# SWITCHING.net
KiCad netlist of a schematic drawn in Altium Designer
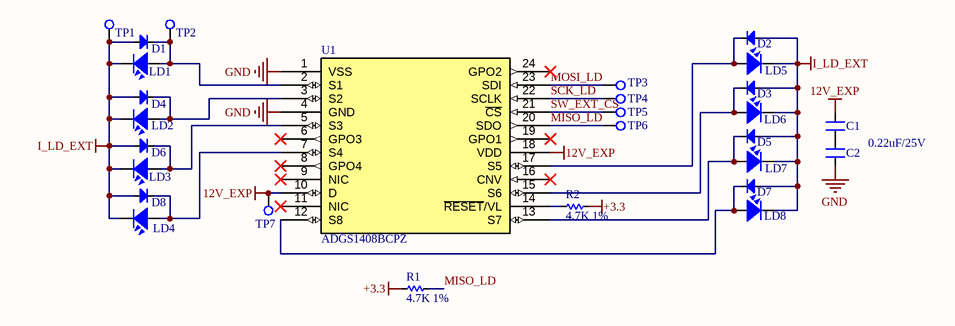
[diagram p0: SWITCHING.SchDoc]

(export (version "E")
  (design (tool "Eeschema 10.0.6"))
  (components
    (comp (ref "C1")
      (value "0.22uF/25V")
      (footprint "SM-0603")
      (description "0603")
      (libsource (lib "Capacitors") (part "CM"))
    )
    (comp (ref "C2")
      (value "0.22uF/25V")
      (footprint "SM-0603")
      (description "0603")
      (libsource (lib "Capacitors") (part "CM"))
    )
    (comp (ref "D1")
      (value "1N4148W-TP")
      (footprint "SOD23")
      (description "DIODE GEN PURP 100V 150MA SOD123")
      (fields (field (name "PUBLISHER") "Altium Limited"))
      (libsource (lib "Library") (part "Diode SMD"))
    )
    (comp (ref "D2")
      (value "1N4148W-TP")
      (footprint "SOD23")
      (description "DIODE GEN PURP 100V 150MA SOD123")
      (fields (field (name "PUBLISHER") "Altium Limited"))
      (libsource (lib "Library") (part "Diode SMD"))
    )
    (comp (ref "D3")
      (value "1N4148W-TP")
      (footprint "SOD23")
      (description "DIODE GEN PURP 100V 150MA SOD123")
      (fields (field (name "PUBLISHER") "Altium Limited"))
      (libsource (lib "Library") (part "Diode SMD"))
    )
    (comp (ref "D4")
      (value "1N4148W-TP")
      (footprint "SOD23")
      (description "DIODE GEN PURP 100V 150MA SOD123")
      (fields (field (name "PUBLISHER") "Altium Limited"))
      (libsource (lib "Library") (part "Diode SMD"))
    )
    (comp (ref "D5")
      (value "1N4148W-TP")
      (footprint "SOD23")
      (description "DIODE GEN PURP 100V 150MA SOD123")
      (fields (field (name "PUBLISHER") "Altium Limited"))
      (libsource (lib "Library") (part "Diode SMD"))
    )
    (comp (ref "D6")
      (value "1N4148W-TP")
      (footprint "SOD23")
      (description "DIODE GEN PURP 100V 150MA SOD123")
      (fields (field (name "PUBLISHER") "Altium Limited"))
      (libsource (lib "Library") (part "Diode SMD"))
    )
    (comp (ref "D7")
      (value "1N4148W-TP")
      (footprint "SOD23")
      (description "DIODE GEN PURP 100V 150MA SOD123")
      (fields (field (name "PUBLISHER") "Altium Limited"))
      (libsource (lib "Library") (part "Diode SMD"))
    )
    (comp (ref "D8")
      (value "1N4148W-TP")
      (footprint "SOD23")
      (description "DIODE GEN PURP 100V 150MA SOD123")
      (fields (field (name "PUBLISHER") "Altium Limited"))
      (libsource (lib "Library") (part "Diode SMD"))
    )
    (comp (ref "LD1") (value "LaserDiode") (footprint "LASER") (libsource (lib "Library") (part "LD")))
    (comp (ref "LD2") (value "LaserDiode") (footprint "LASER") (libsource (lib "Library") (part "LD")))
    (comp (ref "LD3") (value "LaserDiode") (footprint "LASER") (libsource (lib "Library") (part "LD")))
    (comp (ref "LD4") (value "LaserDiode") (footprint "LASER") (libsource (lib "Library") (part "LD")))
    (comp (ref "LD5") (value "LaserDiode") (footprint "LASER") (libsource (lib "Library") (part "LD")))
    (comp (ref "LD6") (value "LaserDiode") (footprint "LASER") (libsource (lib "Library") (part "LD")))
    (comp (ref "LD7") (value "LaserDiode") (footprint "LASER") (libsource (lib "Library") (part "LD")))
    (comp (ref "LD8") (value "LaserDiode") (footprint "LASER") (libsource (lib "Library") (part "LD")))
    (comp (ref "R1")
      (value "4.7K 1%")
      (footprint "RES-SMD-0603")
      (description "0603")
      (fields
        (field (name "MANUFACTURER") "Generic Components")
        (field (name "PUBLISHER") "Altium Hobart Technology Centre")
      )
      (libsource (lib "Library") (part "Res-SMD"))
    )
    (comp (ref "R2")
      (value "4.7K 1%")
      (footprint "RES-SMD-0603")
      (description "0603")
      (fields
        (field (name "MANUFACTURER") "Generic Components")
        (field (name "PUBLISHER") "Altium Hobart Technology Centre")
      )
      (libsource (lib "Library") (part "Res-SMD"))
    )
    (comp (ref "TP1")
      (value "Test_Point")
      (footprint "TESTPOINT")
      (libsource (lib "Library_HUNG") (part "Test_Point"))
    )
    (comp (ref "TP2")
      (value "Test_Point")
      (footprint "TESTPOINT")
      (libsource (lib "Library_HUNG") (part "Test_Point"))
    )
    (comp (ref "TP3")
      (value "Test_Point")
      (footprint "TESTPOINT")
      (libsource (lib "Library_HUNG") (part "Test_Point"))
    )
    (comp (ref "TP4")
      (value "Test_Point")
      (footprint "TESTPOINT")
      (libsource (lib "Library_HUNG") (part "Test_Point"))
    )
    (comp (ref "TP5")
      (value "Test_Point")
      (footprint "TESTPOINT")
      (libsource (lib "Library_HUNG") (part "Test_Point"))
    )
    (comp (ref "TP6")
      (value "Test_Point")
      (footprint "TESTPOINT")
      (libsource (lib "Library_HUNG") (part "Test_Point"))
    )
    (comp (ref "TP7")
      (value "Test_Point")
      (footprint "TESTPOINT")
      (libsource (lib "Library_HUNG") (part "Test_Point"))
    )
    (comp (ref "U1")
      (value "ADGS1408BCPZ")
      (footprint "ADGS1408BCPZ")
      (description "IC MUX 8:1 4.7OHM 24LFCSP")
      (libsource (lib "Library") (part "ADGS1408"))
    )
  )
  (nets
    (net (code "1") (name "+3.3") (class "Default")
      (node (ref "R1") (pin "2") (pinfunction "2_2") (pintype "passive"))
      (node (ref "R2") (pin "1") (pinfunction "1_1") (pintype "passive"))
    )
    (net (code "2") (name "/MISO_LD") (class "Default")
      (node (ref "R1") (pin "1") (pinfunction "1_1") (pintype "passive"))
      (node (ref "TP6") (pin "1") (pintype "power_in"))
      (node (ref "U1") (pin "20") (pinfunction "SDO_20") (pintype "output"))
    )
    (net (code "3") (name "/MOSI_LD") (class "Default")
      (node (ref "TP3") (pin "1") (pintype "power_in"))
      (node (ref "U1") (pin "23") (pinfunction "SDI_23") (pintype "input"))
    )
    (net (code "4") (name "/SCK_LD") (class "Default")
      (node (ref "TP4") (pin "1") (pintype "power_in"))
      (node (ref "U1") (pin "22") (pinfunction "SCLK_22") (pintype "input"))
    )
    (net (code "5") (name "/SW_EXT_CS") (class "Default")
      (node (ref "TP5") (pin "1") (pintype "power_in"))
      (node (ref "U1") (pin "21") (pinfunction "~{CS}_21") (pintype "input"))
    )
    (net (code "6") (name "12V_EXP") (class "Default")
      (node (ref "C1") (pin "2") (pinfunction "2_2") (pintype "passive"))
      (node (ref "TP7") (pin "1") (pintype "power_in"))
      (node (ref "U1") (pin "10") (pinfunction "D_10") (pintype "bidirectional"))
      (node (ref "U1") (pin "18") (pinfunction "VDD_18") (pintype "power_in"))
    )
    (net (code "7") (name "GND") (class "Default")
      (node (ref "C2") (pin "1") (pinfunction "1_1") (pintype "passive"))
      (node (ref "U1") (pin "1") (pinfunction "VSS_1") (pintype "power_in"))
      (node (ref "U1") (pin "4") (pinfunction "GND_4") (pintype "power_in"))
    )
    (net (code "8") (name "I_LD_EXT") (class "Default")
      (node (ref "D1") (pin "1") (pinfunction "A_1") (pintype "passive"))
      (node (ref "D2") (pin "1") (pinfunction "A_1") (pintype "passive"))
      (node (ref "D3") (pin "1") (pinfunction "A_1") (pintype "passive"))
      (node (ref "D4") (pin "1") (pinfunction "A_1") (pintype "passive"))
      (node (ref "D5") (pin "1") (pinfunction "A_1") (pintype "passive"))
      (node (ref "D6") (pin "1") (pinfunction "A_1") (pintype "passive"))
      (node (ref "D7") (pin "1") (pinfunction "A_1") (pintype "passive"))
      (node (ref "D8") (pin "1") (pinfunction "A_1") (pintype "passive"))
      (node (ref "LD1") (pin "3") (pinfunction "3_3") (pintype "passive"))
      (node (ref "LD2") (pin "3") (pinfunction "3_3") (pintype "passive"))
      (node (ref "LD3") (pin "3") (pinfunction "3_3") (pintype "passive"))
      (node (ref "LD4") (pin "3") (pinfunction "3_3") (pintype "passive"))
      (node (ref "LD5") (pin "3") (pinfunction "3_3") (pintype "passive"))
      (node (ref "LD6") (pin "3") (pinfunction "3_3") (pintype "passive"))
      (node (ref "LD7") (pin "3") (pinfunction "3_3") (pintype "passive"))
      (node (ref "LD8") (pin "3") (pinfunction "3_3") (pintype "passive"))
      (node (ref "TP1") (pin "1") (pintype "power_in"))
    )
    (net (code "9") (name "Net-(C1-Pad1)") (class "Default")
      (node (ref "C1") (pin "1") (pinfunction "1_1") (pintype "passive"))
      (node (ref "C2") (pin "2") (pinfunction "2_2") (pintype "passive"))
    )
    (net (code "10") (name "Net-(D1-K)") (class "Default")
      (node (ref "D1") (pin "2") (pinfunction "K_2") (pintype "passive"))
      (node (ref "LD1") (pin "1") (pinfunction "1_1") (pintype "passive"))
      (node (ref "TP2") (pin "1") (pintype "power_in"))
      (node (ref "U1") (pin "2") (pinfunction "S1_2") (pintype "bidirectional"))
    )
    (net (code "11") (name "Net-(D2-K)") (class "Default")
      (node (ref "D2") (pin "2") (pinfunction "K_2") (pintype "passive"))
      (node (ref "LD5") (pin "1") (pinfunction "1_1") (pintype "passive"))
      (node (ref "U1") (pin "17") (pinfunction "S5_17") (pintype "bidirectional"))
    )
    (net (code "12") (name "Net-(D3-K)") (class "Default")
      (node (ref "D3") (pin "2") (pinfunction "K_2") (pintype "passive"))
      (node (ref "LD6") (pin "1") (pinfunction "1_1") (pintype "passive"))
      (node (ref "U1") (pin "15") (pinfunction "S6_15") (pintype "bidirectional"))
    )
    (net (code "13") (name "Net-(D4-K)") (class "Default")
      (node (ref "D4") (pin "2") (pinfunction "K_2") (pintype "passive"))
      (node (ref "LD2") (pin "1") (pinfunction "1_1") (pintype "passive"))
      (node (ref "U1") (pin "3") (pinfunction "S2_3") (pintype "bidirectional"))
    )
    (net (code "14") (name "Net-(D5-K)") (class "Default")
      (node (ref "D5") (pin "2") (pinfunction "K_2") (pintype "passive"))
      (node (ref "LD7") (pin "1") (pinfunction "1_1") (pintype "passive"))
      (node (ref "U1") (pin "13") (pinfunction "S7_13") (pintype "bidirectional"))
    )
    (net (code "15") (name "Net-(D6-K)") (class "Default")
      (node (ref "D6") (pin "2") (pinfunction "K_2") (pintype "passive"))
      (node (ref "LD3") (pin "1") (pinfunction "1_1") (pintype "passive"))
      (node (ref "U1") (pin "5") (pinfunction "S3_5") (pintype "bidirectional"))
    )
    (net (code "16") (name "Net-(D7-K)") (class "Default")
      (node (ref "D7") (pin "2") (pinfunction "K_2") (pintype "passive"))
      (node (ref "LD8") (pin "1") (pinfunction "1_1") (pintype "passive"))
      (node (ref "U1") (pin "12") (pinfunction "S8_12") (pintype "bidirectional"))
    )
    (net (code "17") (name "Net-(D8-K)") (class "Default")
      (node (ref "D8") (pin "2") (pinfunction "K_2") (pintype "passive"))
      (node (ref "LD4") (pin "1") (pinfunction "1_1") (pintype "passive"))
      (node (ref "U1") (pin "7") (pinfunction "S4_7") (pintype "bidirectional"))
    )
    (net (code "18") (name "Net-(U1-~{RESET}{slash}VL)") (class "Default")
      (node (ref "R2") (pin "2") (pinfunction "2_2") (pintype "passive"))
      (node (ref "U1") (pin "14") (pinfunction "~{RESET}/VL_14") (pintype "passive"))
    )
    (net (code "19") (name "unconnected-(U1-CNV-Pad16)") (class "Default")
      (node (ref "U1") (pin "16") (pinfunction "CNV_16") (pintype "input+no_connect"))
    )
    (net (code "20") (name "unconnected-(U1-GPO1-Pad19)") (class "Default")
      (node (ref "U1") (pin "19") (pinfunction "GPO1_19") (pintype "output+no_connect"))
    )
    (net (code "21") (name "unconnected-(U1-GPO2-Pad24)") (class "Default")
      (node (ref "U1") (pin "24") (pinfunction "GPO2_24") (pintype "output+no_connect"))
    )
    (net (code "22") (name "unconnected-(U1-GPO3-Pad6)") (class "Default")
      (node (ref "U1") (pin "6") (pinfunction "GPO3_6") (pintype "output+no_connect"))
    )
    (net (code "23") (name "unconnected-(U1-GPO4-Pad8)") (class "Default")
      (node (ref "U1") (pin "8") (pinfunction "GPO4_8") (pintype "output+no_connect"))
    )
    (net (code "24") (name "unconnected-(U1-NIC-Pad9)") (class "Default")
      (node (ref "U1") (pin "9") (pinfunction "NIC_9") (pintype "passive+no_connect"))
    )
    (net (code "25") (name "unconnected-(U1-NIC-Pad11)") (class "Default")
      (node (ref "U1") (pin "11") (pinfunction "NIC_11") (pintype "passive+no_connect"))
    )
  )
)
